# perch_pcb_v1.net
KiCad netlist of a schematic drawn in EAGLE
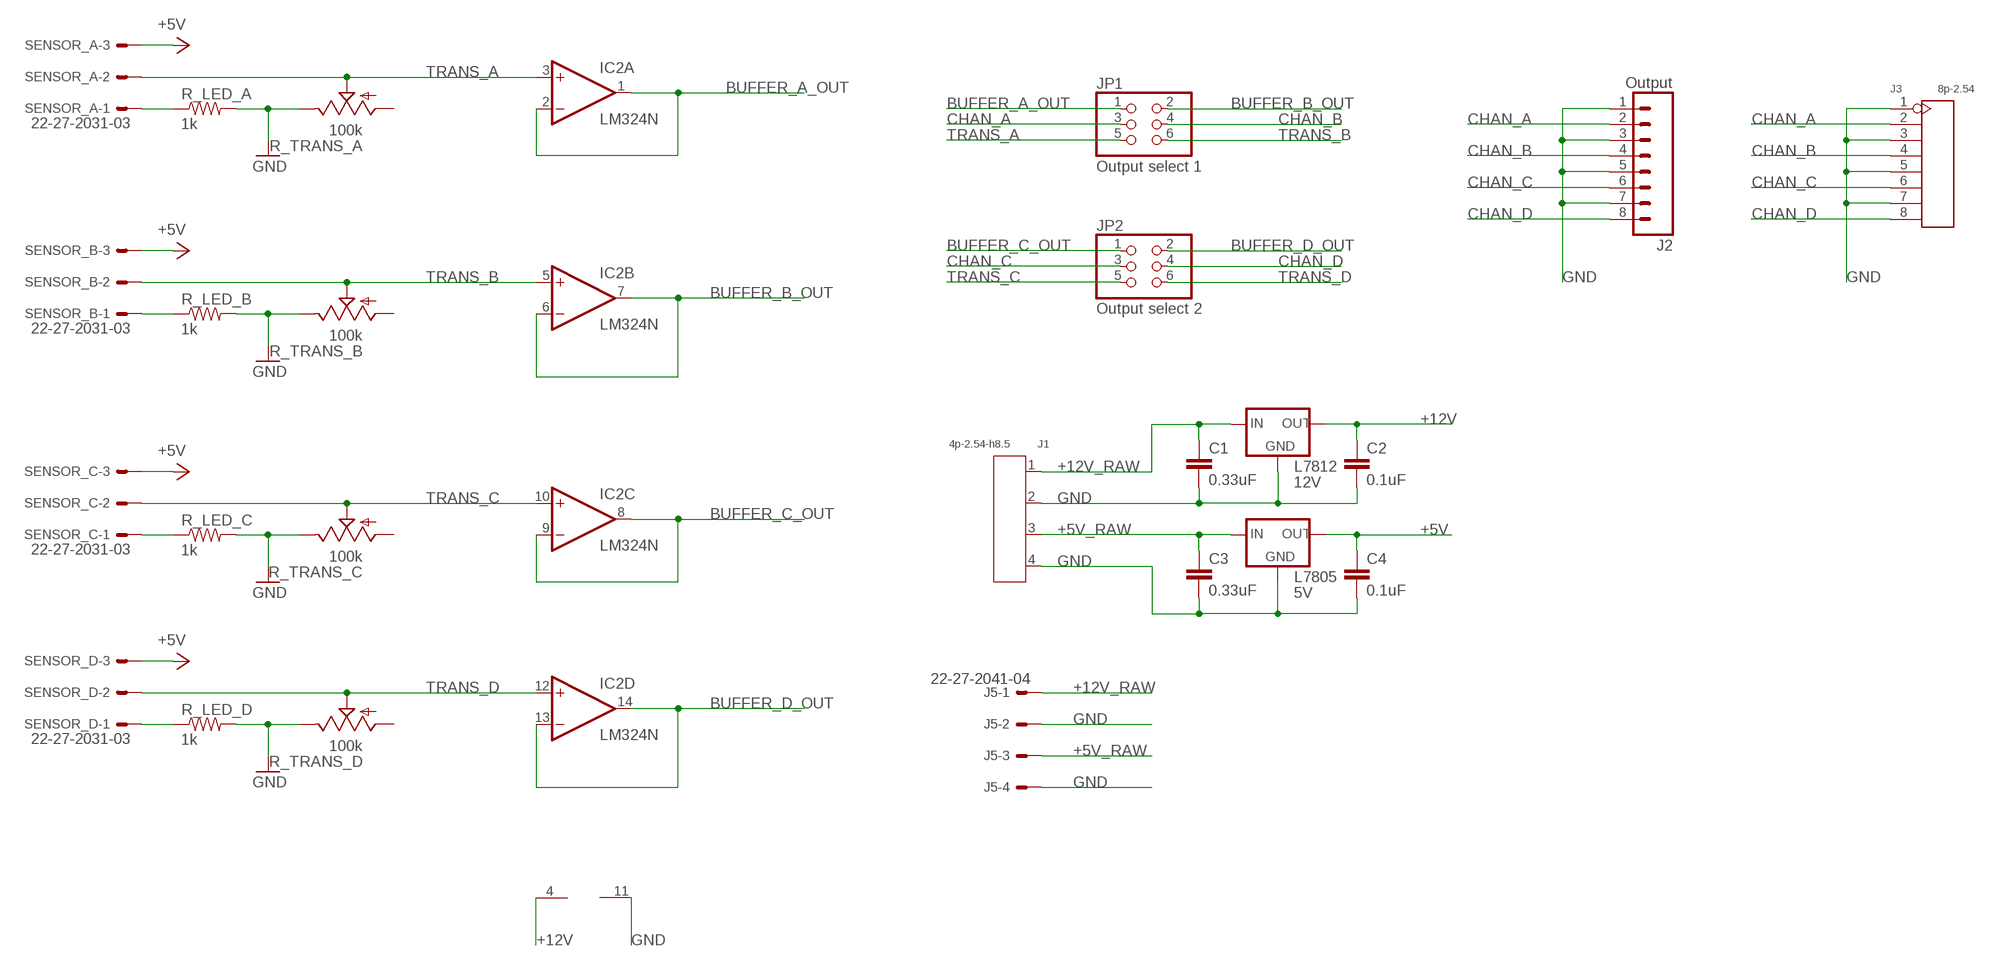
[diagram p0: schematic, sheet 1]

(export (version "E")
  (design (tool "Eeschema 10.0.6"))
  (components
    (comp (ref "C1")
      (value "0.33uF")
      (footprint "eagle-import:CAP-PTH-SMALL")
      (libsource (lib "eagle-import") (part "CAPPTH"))
    )
    (comp (ref "C2")
      (value "0.1uF")
      (footprint "eagle-import:CAP-PTH-SMALL")
      (libsource (lib "eagle-import") (part "CAPPTH"))
    )
    (comp (ref "C3")
      (value "0.33uF")
      (footprint "eagle-import:CAP-PTH-SMALL")
      (libsource (lib "eagle-import") (part "CAPPTH"))
    )
    (comp (ref "C4")
      (value "0.1uF")
      (footprint "eagle-import:CAP-PTH-SMALL")
      (libsource (lib "eagle-import") (part "CAPPTH"))
    )
    (comp (ref "IC2")
      (value "LM324N")
      (footprint "eagle-import:DIL14")
      (libsource (lib "eagle-import") (part "LM324N"))
    )
    (comp (ref "J1")
      (value "4p-2.54-h8.5")
      (footprint "eagle-import:H4-2.54-8.52X6.3MM")
      (fields (field (name "MPN") "GS019-2.54-4P-1"))
      (libsource (lib "eagle-import") (part "DIP-SCREW-TERMINAL-GREEN(4P-2.54-H8.5)"))
    )
    (comp (ref "J2")
      (value "Output")
      (footprint "eagle-import:1X08_ROUND")
      (libsource (lib "eagle-import") (part "M08"))
    )
    (comp (ref "J3")
      (value "8p-2.54")
      (footprint "eagle-import:H8-2.54-18.7X6.3MM")
      (fields (field (name "MPN") "GS019-8P-1"))
      (libsource (lib "eagle-import") (part "DIP-SCREW-TERMINAL(8P-2.54)"))
    )
    (comp (ref "J5")
      (value "22-27-2041-04")
      (footprint "eagle-import:6410-04")
      (libsource (lib "eagle-import") (part "22-?-0427-2041"))
    )
    (comp (ref "JP1")
      (value "Output select 1")
      (footprint "eagle-import:2X03")
      (libsource (lib "eagle-import") (part "PINHD-2X3"))
    )
    (comp (ref "JP2")
      (value "Output select 2")
      (footprint "eagle-import:2X03")
      (libsource (lib "eagle-import") (part "PINHD-2X3"))
    )
    (comp (ref "L7805")
      (value "5V")
      (footprint "eagle-import:TO220-IGO")
      (libsource (lib "eagle-import") (part "V_REG_78XXSINK"))
    )
    (comp (ref "L7812")
      (value "12V")
      (footprint "eagle-import:TO220-IGO")
      (libsource (lib "eagle-import") (part "V_REG_78XXSINK"))
    )
    (comp (ref "R_LED_A")
      (value "1k")
      (footprint "eagle-import:AXIAL-0.3")
      (libsource (lib "eagle-import") (part "RESISTORAXIAL-0.3"))
    )
    (comp (ref "R_LED_B")
      (value "1k")
      (footprint "eagle-import:AXIAL-0.3")
      (libsource (lib "eagle-import") (part "RESISTORAXIAL-0.3"))
    )
    (comp (ref "R_LED_C")
      (value "1k")
      (footprint "eagle-import:AXIAL-0.3")
      (libsource (lib "eagle-import") (part "RESISTORAXIAL-0.3"))
    )
    (comp (ref "R_LED_D")
      (value "1k")
      (footprint "eagle-import:AXIAL-0.3")
      (libsource (lib "eagle-import") (part "RESISTORAXIAL-0.3"))
    )
    (comp (ref "R_TRANS_A")
      (value "100k")
      (footprint "eagle-import:B64W")
      (libsource (lib "eagle-import") (part "TRIM_US-B64W"))
    )
    (comp (ref "R_TRANS_B")
      (value "100k")
      (footprint "eagle-import:B64W")
      (libsource (lib "eagle-import") (part "TRIM_US-B64W"))
    )
    (comp (ref "R_TRANS_C")
      (value "100k")
      (footprint "eagle-import:B64W")
      (libsource (lib "eagle-import") (part "TRIM_US-B64W"))
    )
    (comp (ref "R_TRANS_D")
      (value "100k")
      (footprint "eagle-import:B64W")
      (libsource (lib "eagle-import") (part "TRIM_US-B64W"))
    )
    (comp (ref "SENSOR_A")
      (value "22-27-2031-03")
      (footprint "eagle-import:6410-03")
      (libsource (lib "eagle-import") (part "22-?-0327-2031"))
    )
    (comp (ref "SENSOR_B")
      (value "22-27-2031-03")
      (footprint "eagle-import:6410-03")
      (libsource (lib "eagle-import") (part "22-?-0327-2031"))
    )
    (comp (ref "SENSOR_C")
      (value "22-27-2031-03")
      (footprint "eagle-import:6410-03")
      (libsource (lib "eagle-import") (part "22-?-0327-2031"))
    )
    (comp (ref "SENSOR_D")
      (value "22-27-2031-03")
      (footprint "eagle-import:6410-03")
      (libsource (lib "eagle-import") (part "22-?-0327-2031"))
    )
  )
  (nets
    (net (code "1") (name "+5V") (class "Default")
      (node (ref "C4") (pin "1") (pinfunction "1_1") (pintype "passive"))
      (node (ref "L7805") (pin "OUT") (pinfunction "OUT_OUT") (pintype "passive"))
      (node (ref "SENSOR_A") (pin "3") (pinfunction "S_3") (pintype "passive"))
      (node (ref "SENSOR_B") (pin "3") (pinfunction "S_3") (pintype "passive"))
      (node (ref "SENSOR_C") (pin "3") (pinfunction "S_3") (pintype "passive"))
      (node (ref "SENSOR_D") (pin "3") (pinfunction "S_3") (pintype "passive"))
    )
    (net (code "2") (name "/+5V_RAW") (class "Default")
      (node (ref "C3") (pin "1") (pinfunction "1_1") (pintype "passive"))
      (node (ref "J1") (pin "3") (pinfunction "3_3") (pintype "bidirectional"))
      (node (ref "J5") (pin "3") (pinfunction "S_3") (pintype "passive"))
      (node (ref "L7805") (pin "IN") (pinfunction "IN_IN") (pintype "input"))
    )
    (net (code "3") (name "/+12V") (class "Default")
      (node (ref "C2") (pin "1") (pinfunction "1_1") (pintype "passive"))
      (node (ref "IC2") (pin "4") (pinfunction "V+_4") (pintype "power_in"))
      (node (ref "L7812") (pin "OUT") (pinfunction "OUT_OUT") (pintype "passive"))
    )
    (net (code "4") (name "/+12V_RAW") (class "Default")
      (node (ref "C1") (pin "1") (pinfunction "1_1") (pintype "passive"))
      (node (ref "J1") (pin "1") (pinfunction "1_1") (pintype "bidirectional"))
      (node (ref "J5") (pin "1") (pinfunction "S_1") (pintype "passive"))
      (node (ref "L7812") (pin "IN") (pinfunction "IN_IN") (pintype "input"))
    )
    (net (code "5") (name "/BUFFER_A_OUT") (class "Default")
      (node (ref "IC2") (pin "1") (pinfunction "OUT_1") (pintype "output"))
      (node (ref "IC2") (pin "2") (pinfunction "-IN_2") (pintype "input"))
      (node (ref "JP1") (pin "1") (pinfunction "1_1") (pintype "passive"))
    )
    (net (code "6") (name "/BUFFER_B_OUT") (class "Default")
      (node (ref "IC2") (pin "6") (pinfunction "-IN_6") (pintype "input"))
      (node (ref "IC2") (pin "7") (pinfunction "OUT_7") (pintype "output"))
      (node (ref "JP1") (pin "2") (pinfunction "2_2") (pintype "passive"))
    )
    (net (code "7") (name "/BUFFER_C_OUT") (class "Default")
      (node (ref "IC2") (pin "8") (pinfunction "OUT_8") (pintype "output"))
      (node (ref "IC2") (pin "9") (pinfunction "-IN_9") (pintype "input"))
      (node (ref "JP2") (pin "1") (pinfunction "1_1") (pintype "passive"))
    )
    (net (code "8") (name "/BUFFER_D_OUT") (class "Default")
      (node (ref "IC2") (pin "13") (pinfunction "-IN_13") (pintype "input"))
      (node (ref "IC2") (pin "14") (pinfunction "OUT_14") (pintype "output"))
      (node (ref "JP2") (pin "2") (pinfunction "2_2") (pintype "passive"))
    )
    (net (code "9") (name "/CHAN_A") (class "Default")
      (node (ref "J2") (pin "2") (pinfunction "2_2") (pintype "passive"))
      (node (ref "J3") (pin "2") (pinfunction "2_2") (pintype "bidirectional"))
      (node (ref "JP1") (pin "3") (pinfunction "3_3") (pintype "passive"))
    )
    (net (code "10") (name "/CHAN_B") (class "Default")
      (node (ref "J2") (pin "4") (pinfunction "4_4") (pintype "passive"))
      (node (ref "J3") (pin "4") (pinfunction "4_4") (pintype "bidirectional"))
      (node (ref "JP1") (pin "4") (pinfunction "4_4") (pintype "passive"))
    )
    (net (code "11") (name "/CHAN_C") (class "Default")
      (node (ref "J2") (pin "6") (pinfunction "6_6") (pintype "passive"))
      (node (ref "J3") (pin "6") (pinfunction "6_6") (pintype "bidirectional"))
      (node (ref "JP2") (pin "3") (pinfunction "3_3") (pintype "passive"))
    )
    (net (code "12") (name "/CHAN_D") (class "Default")
      (node (ref "J2") (pin "8") (pinfunction "8_8") (pintype "passive"))
      (node (ref "J3") (pin "8") (pinfunction "8_8") (pintype "bidirectional"))
      (node (ref "JP2") (pin "4") (pinfunction "4_4") (pintype "passive"))
    )
    (net (code "13") (name "/TRANS_A") (class "Default")
      (node (ref "IC2") (pin "3") (pinfunction "+IN_3") (pintype "input"))
      (node (ref "JP1") (pin "5") (pinfunction "5_5") (pintype "passive"))
      (node (ref "R_TRANS_A") (pin "S") (pinfunction "S_S") (pintype "passive"))
      (node (ref "SENSOR_A") (pin "2") (pinfunction "S_2") (pintype "passive"))
    )
    (net (code "14") (name "/TRANS_B") (class "Default")
      (node (ref "IC2") (pin "5") (pinfunction "+IN_5") (pintype "input"))
      (node (ref "JP1") (pin "6") (pinfunction "6_6") (pintype "passive"))
      (node (ref "R_TRANS_B") (pin "S") (pinfunction "S_S") (pintype "passive"))
      (node (ref "SENSOR_B") (pin "2") (pinfunction "S_2") (pintype "passive"))
    )
    (net (code "15") (name "/TRANS_C") (class "Default")
      (node (ref "IC2") (pin "10") (pinfunction "+IN_10") (pintype "input"))
      (node (ref "JP2") (pin "5") (pinfunction "5_5") (pintype "passive"))
      (node (ref "R_TRANS_C") (pin "S") (pinfunction "S_S") (pintype "passive"))
      (node (ref "SENSOR_C") (pin "2") (pinfunction "S_2") (pintype "passive"))
    )
    (net (code "16") (name "/TRANS_D") (class "Default")
      (node (ref "IC2") (pin "12") (pinfunction "+IN_12") (pintype "input"))
      (node (ref "JP2") (pin "6") (pinfunction "6_6") (pintype "passive"))
      (node (ref "R_TRANS_D") (pin "S") (pinfunction "S_S") (pintype "passive"))
      (node (ref "SENSOR_D") (pin "2") (pinfunction "S_2") (pintype "passive"))
    )
    (net (code "17") (name "GND") (class "Default")
      (node (ref "C1") (pin "2") (pinfunction "2_2") (pintype "passive"))
      (node (ref "C2") (pin "2") (pinfunction "2_2") (pintype "passive"))
      (node (ref "C3") (pin "2") (pinfunction "2_2") (pintype "passive"))
      (node (ref "C4") (pin "2") (pinfunction "2_2") (pintype "passive"))
      (node (ref "IC2") (pin "11") (pinfunction "V-_11") (pintype "power_in"))
      (node (ref "J1") (pin "2") (pinfunction "2_2") (pintype "bidirectional"))
      (node (ref "J1") (pin "4") (pinfunction "4_4") (pintype "bidirectional"))
      (node (ref "J2") (pin "1") (pinfunction "1_1") (pintype "passive"))
      (node (ref "J2") (pin "3") (pinfunction "3_3") (pintype "passive"))
      (node (ref "J2") (pin "5") (pinfunction "5_5") (pintype "passive"))
      (node (ref "J2") (pin "7") (pinfunction "7_7") (pintype "passive"))
      (node (ref "J3") (pin "1") (pinfunction "1_1") (pintype "bidirectional"))
      (node (ref "J3") (pin "3") (pinfunction "3_3") (pintype "bidirectional"))
      (node (ref "J3") (pin "5") (pinfunction "5_5") (pintype "bidirectional"))
      (node (ref "J3") (pin "7") (pinfunction "7_7") (pintype "bidirectional"))
      (node (ref "J5") (pin "2") (pinfunction "S_2") (pintype "passive"))
      (node (ref "J5") (pin "4") (pinfunction "S_4") (pintype "passive"))
      (node (ref "L7805") (pin "GND") (pinfunction "GND_GND") (pintype "input"))
      (node (ref "L7812") (pin "GND") (pinfunction "GND_GND") (pintype "input"))
      (node (ref "R_LED_A") (pin "P$2") (pinfunction "2_P$2") (pintype "passive"))
      (node (ref "R_LED_B") (pin "P$2") (pinfunction "2_P$2") (pintype "passive"))
      (node (ref "R_LED_C") (pin "P$2") (pinfunction "2_P$2") (pintype "passive"))
      (node (ref "R_LED_D") (pin "P$2") (pinfunction "2_P$2") (pintype "passive"))
      (node (ref "R_TRANS_A") (pin "E") (pinfunction "E_E") (pintype "passive"))
      (node (ref "R_TRANS_B") (pin "E") (pinfunction "E_E") (pintype "passive"))
      (node (ref "R_TRANS_C") (pin "E") (pinfunction "E_E") (pintype "passive"))
      (node (ref "R_TRANS_D") (pin "E") (pinfunction "E_E") (pintype "passive"))
    )
    (net (code "18") (name "Net-(R_LED_A-1)") (class "Default")
      (node (ref "R_LED_A") (pin "P$1") (pinfunction "1_P$1") (pintype "passive"))
      (node (ref "SENSOR_A") (pin "1") (pinfunction "S_1") (pintype "passive"))
    )
    (net (code "19") (name "Net-(R_LED_B-1)") (class "Default")
      (node (ref "R_LED_B") (pin "P$1") (pinfunction "1_P$1") (pintype "passive"))
      (node (ref "SENSOR_B") (pin "1") (pinfunction "S_1") (pintype "passive"))
    )
    (net (code "20") (name "Net-(R_LED_C-1)") (class "Default")
      (node (ref "R_LED_C") (pin "P$1") (pinfunction "1_P$1") (pintype "passive"))
      (node (ref "SENSOR_C") (pin "1") (pinfunction "S_1") (pintype "passive"))
    )
    (net (code "21") (name "Net-(R_LED_D-1)") (class "Default")
      (node (ref "R_LED_D") (pin "P$1") (pinfunction "1_P$1") (pintype "passive"))
      (node (ref "SENSOR_D") (pin "1") (pinfunction "S_1") (pintype "passive"))
    )
    (net (code "22") (name "unconnected-(R_TRANS_A-PadA)") (class "Default")
      (node (ref "R_TRANS_A") (pin "A") (pinfunction "A_A") (pintype "passive"))
    )
    (net (code "23") (name "unconnected-(R_TRANS_B-PadA)") (class "Default")
      (node (ref "R_TRANS_B") (pin "A") (pinfunction "A_A") (pintype "passive"))
    )
    (net (code "24") (name "unconnected-(R_TRANS_C-PadA)") (class "Default")
      (node (ref "R_TRANS_C") (pin "A") (pinfunction "A_A") (pintype "passive"))
    )
    (net (code "25") (name "unconnected-(R_TRANS_D-PadA)") (class "Default")
      (node (ref "R_TRANS_D") (pin "A") (pinfunction "A_A") (pintype "passive"))
    )
  )
)
